# PCB_Project_Wavelength.net
KiCad netlist of a schematic drawn in Altium Designer
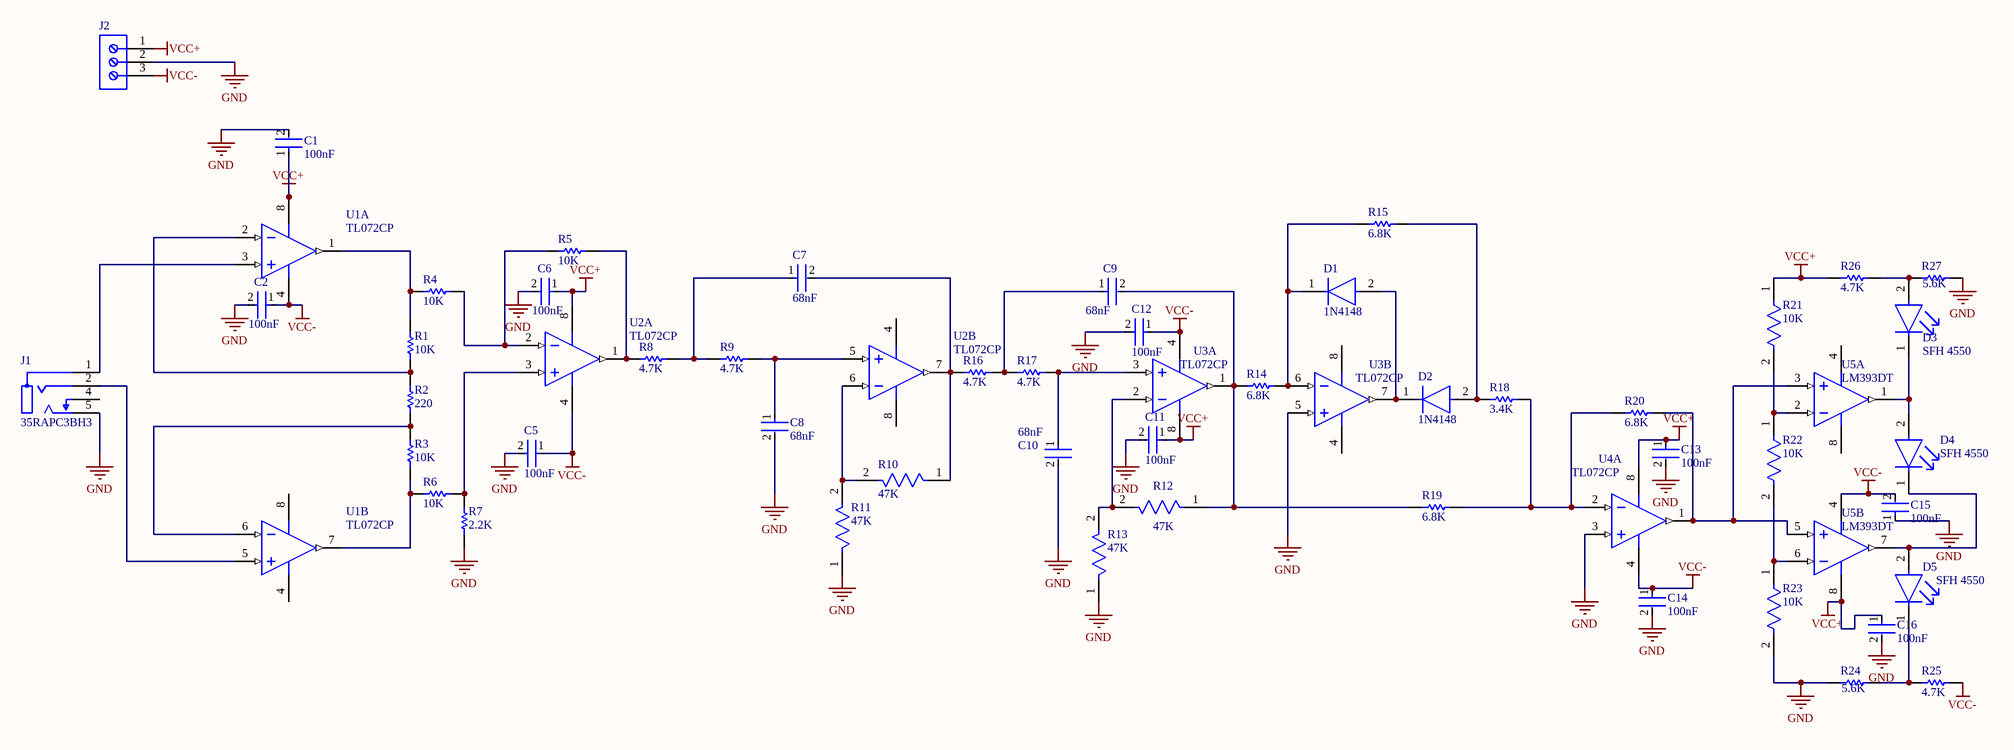
[diagram p0: PCB_Project_Wavelength.SchDoc]

(export (version "E")
  (design (tool "Eeschema 10.0.6"))
  (components
    (comp (ref "C1")
      (value "100nF")
      (footprint "FP-CGA3E-0_3-0_1-IPC_A")
      (description "Cap Ceramic 100nF 50V X7R 10% Pad SMD 0603 +125°C Automotive T/R")
      (fields (field (name "TOLERANCE") "10%") (field (name "VOLTAGE") "50V"))
      (libsource (lib "Altium Content Vault") (part "b4654b650e69147ec39a6b967a45e02"))
    )
    (comp (ref "C2")
      (value "100nF")
      (footprint "FP-CGA3E-0_3-0_1-IPC_A")
      (description "Cap Ceramic 100nF 50V X7R 10% Pad SMD 0603 +125°C Automotive T/R")
      (fields (field (name "TOLERANCE") "10%") (field (name "VOLTAGE") "50V"))
      (libsource (lib "Altium Content Vault") (part "b4654b650e69147ec39a6b967a45e02"))
    )
    (comp (ref "C5")
      (value "100nF")
      (footprint "FP-CGA3E-0_3-0_1-IPC_A")
      (description "Cap Ceramic 100nF 50V X7R 10% Pad SMD 0603 +125°C Automotive T/R")
      (fields (field (name "TOLERANCE") "10%") (field (name "VOLTAGE") "50V"))
      (libsource (lib "Altium Content Vault") (part "b4654b650e69147ec39a6b967a45e02"))
    )
    (comp (ref "C6")
      (value "100nF")
      (footprint "FP-CGA3E-0_3-0_1-IPC_A")
      (description "Cap Ceramic 100nF 50V X7R 10% Pad SMD 0603 +125°C Automotive T/R")
      (fields (field (name "TOLERANCE") "10%") (field (name "VOLTAGE") "50V"))
      (libsource (lib "Altium Content Vault") (part "b4654b650e69147ec39a6b967a45e02"))
    )
    (comp (ref "C7")
      (value "68nF")
      (footprint "FP-1206-L_3_2_0_2-W_1_6_0-IPC_A")
      (description "General Purpose Ceramic Capacitor, 1206, 68nF, 10%, X7R, 15%, 100V")
      (fields (field (name "VOLTAGE") "100V") (field (name "TOLERANCE") "10%"))
      (libsource (lib "Altium Content Vault") (part "02cd4be3c70576c341d710602a673aa"))
    )
    (comp (ref "C8")
      (value "68nF")
      (footprint "FP-1206-L_3_2_0_2-W_1_6_0-IPC_A")
      (description "General Purpose Ceramic Capacitor, 1206, 68nF, 10%, X7R, 15%, 100V")
      (fields (field (name "VOLTAGE") "100V") (field (name "TOLERANCE") "10%"))
      (libsource (lib "Altium Content Vault") (part "02cd4be3c70576c341d710602a673aa"))
    )
    (comp (ref "C9")
      (value "68nF")
      (footprint "FP-1206-L_3_2_0_2-W_1_6_0-IPC_A")
      (description "General Purpose Ceramic Capacitor, 1206, 68nF, 10%, X7R, 15%, 100V")
      (fields (field (name "VOLTAGE") "100V") (field (name "TOLERANCE") "10%"))
      (libsource (lib "Altium Content Vault") (part "02cd4be3c70576c341d710602a673aa"))
    )
    (comp (ref "C10")
      (value "68nF")
      (footprint "FP-1206-L_3_2_0_2-W_1_6_0-IPC_A")
      (description "General Purpose Ceramic Capacitor, 1206, 68nF, 10%, X7R, 15%, 100V")
      (fields (field (name "VOLTAGE") "100V") (field (name "TOLERANCE") "10%"))
      (libsource (lib "Altium Content Vault") (part "02cd4be3c70576c341d710602a673aa"))
    )
    (comp (ref "C11")
      (value "100nF")
      (footprint "FP-CGA3E-0_3-0_1-IPC_A")
      (description "Cap Ceramic 100nF 50V X7R 10% Pad SMD 0603 +125°C Automotive T/R")
      (fields (field (name "TOLERANCE") "10%") (field (name "VOLTAGE") "50V"))
      (libsource (lib "Altium Content Vault") (part "b4654b650e69147ec39a6b967a45e02"))
    )
    (comp (ref "C12")
      (value "100nF")
      (footprint "FP-CGA3E-0_3-0_1-IPC_A")
      (description "Cap Ceramic 100nF 50V X7R 10% Pad SMD 0603 +125°C Automotive T/R")
      (fields (field (name "TOLERANCE") "10%") (field (name "VOLTAGE") "50V"))
      (libsource (lib "Altium Content Vault") (part "b4654b650e69147ec39a6b967a45e02"))
    )
    (comp (ref "C13")
      (value "100nF")
      (footprint "FP-CGA3E-0_3-0_1-IPC_A")
      (description "Cap Ceramic 100nF 50V X7R 10% Pad SMD 0603 +125°C Automotive T/R")
      (fields (field (name "TOLERANCE") "10%") (field (name "VOLTAGE") "50V"))
      (libsource (lib "Altium Content Vault") (part "b4654b650e69147ec39a6b967a45e02"))
    )
    (comp (ref "C14")
      (value "100nF")
      (footprint "FP-CGA3E-0_3-0_1-IPC_A")
      (description "Cap Ceramic 100nF 50V X7R 10% Pad SMD 0603 +125°C Automotive T/R")
      (fields (field (name "TOLERANCE") "10%") (field (name "VOLTAGE") "50V"))
      (libsource (lib "Altium Content Vault") (part "b4654b650e69147ec39a6b967a45e02"))
    )
    (comp (ref "C15")
      (value "100nF")
      (footprint "FP-CGA3E-0_3-0_1-IPC_A")
      (description "Cap Ceramic 100nF 50V X7R 10% Pad SMD 0603 +125°C Automotive T/R")
      (fields (field (name "TOLERANCE") "10%") (field (name "VOLTAGE") "50V"))
      (libsource (lib "Altium Content Vault") (part "b4654b650e69147ec39a6b967a45e02"))
    )
    (comp (ref "C16")
      (value "100nF")
      (footprint "FP-CGA3E-0_3-0_1-IPC_A")
      (description "Cap Ceramic 100nF 50V X7R 10% Pad SMD 0603 +125°C Automotive T/R")
      (fields (field (name "TOLERANCE") "10%") (field (name "VOLTAGE") "50V"))
      (libsource (lib "Altium Content Vault") (part "b4654b650e69147ec39a6b967a45e02"))
    )
    (comp (ref "D1")
      (value "1N4148")
      (footprint "FP-017AG-MFG")
      (description "DIODE GEN PURP 100V 200MA DO35")
      (fields (field (name "VOLTAGE") "100V"))
      (libsource (lib "Altium Content Vault") (part "d7152d700b627762746794eb795d46e"))
    )
    (comp (ref "D2")
      (value "1N4148")
      (footprint "FP-017AG-MFG")
      (description "DIODE GEN PURP 100V 200MA DO35")
      (fields (field (name "VOLTAGE") "100V"))
      (libsource (lib "Altium Content Vault") (part "d7152d700b627762746794eb795d46e"))
    )
    (comp (ref "D3")
      (value "SFH 4550")
      (footprint "FP-SFH_4550-MFG")
      (description "EMITTER IR 860NM 100MA RADIAL")
      (fields
        (field (name "OCTOPART") "https://octopart.com/sfh+4550-osram+opto-55410894")
        (field (name "MANUFACTURER") "Osram Opto")
      )
      (libsource (lib "Altium Content Vault") (part "75a0115997dd6a71327e26aab64f6f8"))
    )
    (comp (ref "D4")
      (value "SFH 4550")
      (footprint "FP-SFH_4550-MFG")
      (description "EMITTER IR 860NM 100MA RADIAL")
      (fields
        (field (name "OCTOPART") "https://octopart.com/sfh+4550-osram+opto-55410894")
        (field (name "MANUFACTURER") "Osram Opto")
      )
      (libsource (lib "Altium Content Vault") (part "75a0115997dd6a71327e26aab64f6f8"))
    )
    (comp (ref "D5")
      (value "SFH 4550")
      (footprint "FP-SFH_4550-MFG")
      (description "EMITTER IR 860NM 100MA RADIAL")
      (fields
        (field (name "OCTOPART") "https://octopart.com/sfh+4550-osram+opto-55410894")
        (field (name "MANUFACTURER") "Osram Opto")
      )
      (libsource (lib "Altium Content Vault") (part "75a0115997dd6a71327e26aab64f6f8"))
    )
    (comp (ref "J1")
      (value "35RAPC3BH3")
      (footprint "FP-35RAPC3BH3-MFG")
      (description "CONN JACK STEREO 3.5MM R/A")
      (libsource (lib "Altium Content Vault") (part "6593a1246df2d7246a2ad7da18ee256"))
    )
    (comp (ref "J2")
      (value "691709710303")
      (footprint "691709710303")
      (description "Battery connector")
      (fields (field (name "VOLTAGE") "300V"))
      (libsource (lib "Altium Content Vault") (part "TBL - 1R - 03P - Screw"))
    )
    (comp (ref "R1")
      (value "10K")
      (footprint "RESC1609X50X30NL8T20")
      (description "Chip Resistor, 10 KOhm, +/- 1%, 100 mW, -55 to 155 degC, 0603 (1608 Metric), RoHS, Tape and Reel")
      (fields (field (name "MANUFACTURER") "Vishay Semiconductor"))
      (libsource (lib "Altium Content Vault") (part "RES-2"))
    )
    (comp (ref "R2")
      (value "220")
      (footprint "RESC2013X70X40NL20T20")
      (fields (field (name "PART NUMBER") "ERJ6ENF2200V") (field (name "MANUFACTURER") "Panasonic"))
      (libsource (lib "Altium Content Vault") (part "RES"))
    )
    (comp (ref "R3")
      (value "10K")
      (footprint "RESC1609X50X30NL8T20")
      (description "Chip Resistor, 10 KOhm, +/- 1%, 100 mW, -55 to 155 degC, 0603 (1608 Metric), RoHS, Tape and Reel")
      (fields (field (name "MANUFACTURER") "Vishay Semiconductor"))
      (libsource (lib "Altium Content Vault") (part "RES-2"))
    )
    (comp (ref "R4")
      (value "10K")
      (footprint "RESC1609X50X30NL8T20")
      (description "Chip Resistor, 10 KOhm, +/- 1%, 100 mW, -55 to 155 degC, 0603 (1608 Metric), RoHS, Tape and Reel")
      (fields (field (name "MANUFACTURER") "Vishay Semiconductor"))
      (libsource (lib "Altium Content Vault") (part "RES-2"))
    )
    (comp (ref "R5")
      (value "10K")
      (footprint "RESC1609X50X30NL8T20")
      (description "Chip Resistor, 10 KOhm, +/- 1%, 100 mW, -55 to 155 degC, 0603 (1608 Metric), RoHS, Tape and Reel")
      (fields (field (name "MANUFACTURER") "Vishay Semiconductor"))
      (libsource (lib "Altium Content Vault") (part "RES-2"))
    )
    (comp (ref "R6")
      (value "10K")
      (footprint "RESC1609X50X30NL8T20")
      (description "Chip Resistor, 10 KOhm, +/- 1%, 100 mW, -55 to 155 degC, 0603 (1608 Metric), RoHS, Tape and Reel")
      (fields (field (name "MANUFACTURER") "Vishay Semiconductor"))
      (libsource (lib "Altium Content Vault") (part "RES-2"))
    )
    (comp (ref "R7")
      (value "2.2K")
      (footprint "RESC1608X55X25LL10T15")
      (fields (field (name "TOLERANCE") "1%") (field (name "MANUFACTURER") "Yageo"))
      (libsource (lib "Altium Content Vault") (part "RES-2"))
    )
    (comp (ref "R8")
      (value "4.7K")
      (footprint "RESC1005X40X25LL05T05")
      (description "Chip Resistor, 4.7 KOhm, +/- 1%, 0.1 W, -55 to 155 degC, 0402 (1005 Metric), RoHS, Tape and Reel")
      (fields (field (name "TOLERANCE") "1%") (field (name "PARTNUMBER") "ERJ-2RKF4701X"))
      (libsource (lib "Altium Content Vault") (part "RES-2"))
    )
    (comp (ref "R9")
      (value "4.7K")
      (footprint "RESC1005X40X25LL05T05")
      (description "Chip Resistor, 4.7 KOhm, +/- 1%, 0.1 W, -55 to 155 degC, 0402 (1005 Metric), RoHS, Tape and Reel")
      (fields (field (name "TOLERANCE") "1%") (field (name "PARTNUMBER") "ERJ-2RKF4701X"))
      (libsource (lib "Altium Content Vault") (part "RES-2"))
    )
    (comp (ref "R10")
      (value "47K")
      (footprint "FP-CRCW0603-e3-IPC_B")
      (description "RES SMD 47K OHM 1% 1/10W 0603")
      (fields (field (name "TOLERANCE") "1%"))
      (libsource (lib "Altium Content Vault") (part "1029c3af85768c4190bb7ad29bc67b5"))
    )
    (comp (ref "R11")
      (value "47K")
      (footprint "FP-CRCW0603-e3-IPC_B")
      (description "RES SMD 47K OHM 1% 1/10W 0603")
      (fields (field (name "TOLERANCE") "1%"))
      (libsource (lib "Altium Content Vault") (part "1029c3af85768c4190bb7ad29bc67b5"))
    )
    (comp (ref "R12")
      (value "47K")
      (footprint "FP-CRCW0603-e3-IPC_B")
      (description "RES SMD 47K OHM 1% 1/10W 0603")
      (fields (field (name "TOLERANCE") "1%"))
      (libsource (lib "Altium Content Vault") (part "1029c3af85768c4190bb7ad29bc67b5"))
    )
    (comp (ref "R13")
      (value "47K")
      (footprint "FP-CRCW0603-e3-IPC_B")
      (description "RES SMD 47K OHM 1% 1/10W 0603")
      (fields (field (name "TOLERANCE") "1%"))
      (libsource (lib "Altium Content Vault") (part "1029c3af85768c4190bb7ad29bc67b5"))
    )
    (comp (ref "R14")
      (value "6.8K")
      (footprint "RESC1609X50X30LL10T20")
      (fields (field (name "PART NUMBER") "CRCW06036K80FKEA") (field (name "MANUFACTURER") "Vishay Dale"))
      (libsource (lib "Altium Content Vault") (part "RES"))
    )
    (comp (ref "R15")
      (value "6.8K")
      (footprint "RESC1609X50X30LL10T20")
      (fields (field (name "PART NUMBER") "CRCW06036K80FKEA") (field (name "MANUFACTURER") "Vishay Dale"))
      (libsource (lib "Altium Content Vault") (part "RES"))
    )
    (comp (ref "R16")
      (value "4.7K")
      (footprint "RESC1005X40X25LL05T05")
      (description "Chip Resistor, 4.7 KOhm, +/- 1%, 0.1 W, -55 to 155 degC, 0402 (1005 Metric), RoHS, Tape and Reel")
      (fields (field (name "TOLERANCE") "1%") (field (name "PARTNUMBER") "ERJ-2RKF4701X"))
      (libsource (lib "Altium Content Vault") (part "RES-2"))
    )
    (comp (ref "R17")
      (value "4.7K")
      (footprint "RESC1005X40X25LL05T05")
      (description "Chip Resistor, 4.7 KOhm, +/- 1%, 0.1 W, -55 to 155 degC, 0402 (1005 Metric), RoHS, Tape and Reel")
      (fields (field (name "TOLERANCE") "1%") (field (name "PARTNUMBER") "ERJ-2RKF4701X"))
      (libsource (lib "Altium Content Vault") (part "RES-2"))
    )
    (comp (ref "R18")
      (value "3.4K")
      (footprint "RESC1609X50X30LL10T20")
      (fields (field (name "MANUFACTURER") "Vishay Dale") (field (name "PART NUMBER") "CRCW06033K40FKEA"))
      (libsource (lib "Altium Content Vault") (part "RES"))
    )
    (comp (ref "R19")
      (value "6.8K")
      (footprint "RESC1609X50X30LL10T20")
      (fields (field (name "PART NUMBER") "CRCW06036K80FKEA") (field (name "MANUFACTURER") "Vishay Dale"))
      (libsource (lib "Altium Content Vault") (part "RES"))
    )
    (comp (ref "R20")
      (value "6.8K")
      (footprint "RESC1609X50X30LL10T20")
      (fields (field (name "PART NUMBER") "CRCW06036K80FKEA") (field (name "MANUFACTURER") "Vishay Dale"))
      (libsource (lib "Altium Content Vault") (part "RES"))
    )
    (comp (ref "R21")
      (value "10K")
      (footprint "FP-MCT0603-IPC_C")
      (description "RES SMD 100 OHM 1% 1/8W 0603")
      (fields (field (name "TOLERANCE") "1%"))
      (libsource (lib "Altium Content Vault") (part "1029c3af85768c4190bb7ad29bc67b5"))
    )
    (comp (ref "R22")
      (value "10K")
      (footprint "FP-MCT0603-IPC_C")
      (description "RES SMD 100 OHM 1% 1/8W 0603")
      (fields (field (name "TOLERANCE") "1%"))
      (libsource (lib "Altium Content Vault") (part "1029c3af85768c4190bb7ad29bc67b5"))
    )
    (comp (ref "R23")
      (value "10K")
      (footprint "FP-MCT0603-IPC_C")
      (description "RES SMD 100 OHM 1% 1/8W 0603")
      (fields (field (name "TOLERANCE") "1%"))
      (libsource (lib "Altium Content Vault") (part "1029c3af85768c4190bb7ad29bc67b5"))
    )
    (comp (ref "R24")
      (value "5.6K")
      (footprint "RESC1005X40X25LL05T05")
      (fields (field (name "MANUFACTURER") "Vishay Dale") (field (name "PART NUMBER") "CRCW04025K60FKED"))
      (libsource (lib "Altium Content Vault") (part "RES"))
    )
    (comp (ref "R25")
      (value "4.7K")
      (footprint "RESC2013X70X40NL20T20")
      (description "Chip Resistor, 4.7 KOhm, +/- 1%, 0.125 W, -55 to 155 degC, 0805 (2012 Metric), RoHS, Tape and Reel")
      (fields (field (name "MANUFACTURER") "Panasonic"))
      (libsource (lib "Altium Content Vault") (part "RES-2"))
    )
    (comp (ref "R26")
      (value "4.7K")
      (footprint "RESC2013X70X40NL20T20")
      (description "Chip Resistor, 4.7 KOhm, +/- 1%, 0.125 W, -55 to 155 degC, 0805 (2012 Metric), RoHS, Tape and Reel")
      (fields (field (name "MANUFACTURER") "Panasonic"))
      (libsource (lib "Altium Content Vault") (part "RES-2"))
    )
    (comp (ref "R27")
      (value "5.6K")
      (footprint "RESC1005X40X25LL05T05")
      (fields (field (name "MANUFACTURER") "Vishay Dale") (field (name "PART NUMBER") "CRCW04025K60FKED"))
      (libsource (lib "Altium Content Vault") (part "RES"))
    )
    (comp (ref "U1")
      (value "TL072CP")
      (footprint "P0008A")
      (fields (field (name "MANUFACTURER") "Texas Instruments"))
      (libsource (lib "Altium Content Vault") (part "TI-AMP-D6-2-8_D"))
    )
    (comp (ref "U2")
      (value "TL072CP")
      (footprint "P0008A")
      (fields (field (name "MANUFACTURER") "Texas Instruments"))
      (libsource (lib "Altium Content Vault") (part "TI-AMP-D6-2-8_D"))
    )
    (comp (ref "U3")
      (value "TL072CP")
      (footprint "P0008A")
      (fields (field (name "MANUFACTURER") "Texas Instruments"))
      (libsource (lib "Altium Content Vault") (part "TI-AMP-D6-2-8_D"))
    )
    (comp (ref "U4")
      (value "TL072CP")
      (footprint "P0008A")
      (fields (field (name "MANUFACTURER") "Texas Instruments"))
      (libsource (lib "Altium Content Vault") (part "TI-AMP-D6-2-8_D"))
    )
    (comp (ref "U5")
      (value "LM393DT")
      (footprint "STM-SO-8_D_L")
      (description "Low-Power, Dual-Voltage Comparator, 2 to 36 V, 0 to 70 degC, 8-Pin SOIC (SO), RoHS, Tape and Reel")
      (fields (field (name "MANUFACTURER") "STMicroelectronics"))
      (libsource (lib "Altium Content Vault") (part "STM-LM393-SO8"))
    )
  )
  (nets
    (net (code "1") (name "GND") (class "Default")
      (node (ref "C1") (pin "2") (pinfunction "2_2") (pintype "passive"))
      (node (ref "C10") (pin "2") (pinfunction "2_2") (pintype "passive"))
      (node (ref "C11") (pin "2") (pinfunction "2_2") (pintype "passive"))
      (node (ref "C12") (pin "2") (pinfunction "2_2") (pintype "passive"))
      (node (ref "C13") (pin "2") (pinfunction "2_2") (pintype "passive"))
      (node (ref "C14") (pin "2") (pinfunction "2_2") (pintype "passive"))
      (node (ref "C15") (pin "1") (pinfunction "1_1") (pintype "passive"))
      (node (ref "C16") (pin "2") (pinfunction "2_2") (pintype "passive"))
      (node (ref "C2") (pin "2") (pinfunction "2_2") (pintype "passive"))
      (node (ref "C5") (pin "2") (pinfunction "2_2") (pintype "passive"))
      (node (ref "C6") (pin "2") (pinfunction "2_2") (pintype "passive"))
      (node (ref "C8") (pin "2") (pinfunction "2_2") (pintype "passive"))
      (node (ref "J1") (pin "5") (pinfunction "5_5") (pintype "passive"))
      (node (ref "J2") (pin "2") (pinfunction "2_2") (pintype "passive"))
      (node (ref "R11") (pin "1") (pinfunction "1_1") (pintype "passive"))
      (node (ref "R13") (pin "1") (pinfunction "1_1") (pintype "passive"))
      (node (ref "R23") (pin "2") (pinfunction "2_2") (pintype "passive"))
      (node (ref "R24") (pin "1") (pinfunction "1_1") (pintype "passive"))
      (node (ref "R27") (pin "2") (pinfunction "2_2") (pintype "passive"))
      (node (ref "R7") (pin "1") (pinfunction "1_1") (pintype "passive"))
      (node (ref "U3") (pin "5") (pinfunction "IN2+_5") (pintype "input"))
      (node (ref "U4") (pin "3") (pinfunction "IN1+_3") (pintype "input"))
    )
    (net (code "2") (name "Net-(C7-Pad1)") (class "Default")
      (node (ref "C7") (pin "1") (pinfunction "1_1") (pintype "passive"))
      (node (ref "R8") (pin "2") (pinfunction "2_2") (pintype "passive"))
      (node (ref "R9") (pin "1") (pinfunction "1_1") (pintype "passive"))
    )
    (net (code "3") (name "Net-(C9-Pad1)") (class "Default")
      (node (ref "C9") (pin "1") (pinfunction "1_1") (pintype "passive"))
      (node (ref "R16") (pin "2") (pinfunction "2_2") (pintype "passive"))
      (node (ref "R17") (pin "1") (pinfunction "1_1") (pintype "passive"))
    )
    (net (code "4") (name "Net-(D1-A)") (class "Default")
      (node (ref "D1") (pin "2") (pinfunction "A_2") (pintype "passive"))
      (node (ref "D2") (pin "1") (pinfunction "C_1") (pintype "passive"))
      (node (ref "U3") (pin "7") (pinfunction "OUT2_7") (pintype "output"))
    )
    (net (code "5") (name "Net-(D1-C)") (class "Default")
      (node (ref "D1") (pin "1") (pinfunction "C_1") (pintype "passive"))
      (node (ref "R14") (pin "2") (pinfunction "2_2") (pintype "passive"))
      (node (ref "R15") (pin "1") (pinfunction "1_1") (pintype "passive"))
      (node (ref "U3") (pin "6") (pinfunction "IN2-_6") (pintype "input"))
    )
    (net (code "6") (name "Net-(D2-A)") (class "Default")
      (node (ref "D2") (pin "2") (pinfunction "A_2") (pintype "passive"))
      (node (ref "R15") (pin "2") (pinfunction "2_2") (pintype "passive"))
      (node (ref "R18") (pin "1") (pinfunction "1_1") (pintype "passive"))
    )
    (net (code "7") (name "Net-(D3-A)") (class "Default")
      (node (ref "D3") (pin "2") (pinfunction "A_2") (pintype "passive"))
      (node (ref "R26") (pin "2") (pinfunction "2_2") (pintype "passive"))
      (node (ref "R27") (pin "1") (pinfunction "1_1") (pintype "passive"))
    )
    (net (code "8") (name "Net-(D3-C)") (class "Default")
      (node (ref "D3") (pin "1") (pinfunction "C_1") (pintype "passive"))
      (node (ref "D4") (pin "2") (pinfunction "A_2") (pintype "passive"))
      (node (ref "U5") (pin "1") (pinfunction "OUT1_1") (pintype "output"))
    )
    (net (code "9") (name "Net-(D4-C)") (class "Default")
      (node (ref "D4") (pin "1") (pinfunction "C_1") (pintype "passive"))
      (node (ref "D5") (pin "2") (pinfunction "A_2") (pintype "passive"))
      (node (ref "U5") (pin "7") (pinfunction "OUT2_7") (pintype "output"))
    )
    (net (code "10") (name "Net-(D5-C)") (class "Default")
      (node (ref "D5") (pin "1") (pinfunction "C_1") (pintype "passive"))
      (node (ref "R24") (pin "2") (pinfunction "2_2") (pintype "passive"))
      (node (ref "R25") (pin "1") (pinfunction "1_1") (pintype "passive"))
    )
    (net (code "11") (name "Net-(U1A-IN1+)") (class "Default")
      (node (ref "J1") (pin "1") (pinfunction "1_1") (pintype "passive"))
      (node (ref "U1") (pin "3") (pinfunction "IN1+_3") (pintype "input"))
    )
    (net (code "12") (name "Net-(U1A-IN1-)") (class "Default")
      (node (ref "R1") (pin "1") (pinfunction "1_1") (pintype "passive"))
      (node (ref "R2") (pin "2") (pinfunction "2_2") (pintype "passive"))
      (node (ref "U1") (pin "2") (pinfunction "IN1-_2") (pintype "input"))
    )
    (net (code "13") (name "Net-(U1A-OUT1)") (class "Default")
      (node (ref "R1") (pin "2") (pinfunction "2_2") (pintype "passive"))
      (node (ref "R4") (pin "2") (pinfunction "2_2") (pintype "passive"))
      (node (ref "U1") (pin "1") (pinfunction "OUT1_1") (pintype "output"))
    )
    (net (code "14") (name "Net-(U1B-IN2+)") (class "Default")
      (node (ref "J1") (pin "2") (pinfunction "2_2") (pintype "passive"))
      (node (ref "U1") (pin "5") (pinfunction "IN2+_5") (pintype "input"))
    )
    (net (code "15") (name "Net-(U1B-IN2-)") (class "Default")
      (node (ref "R2") (pin "1") (pinfunction "1_1") (pintype "passive"))
      (node (ref "R3") (pin "2") (pinfunction "2_2") (pintype "passive"))
      (node (ref "U1") (pin "6") (pinfunction "IN2-_6") (pintype "input"))
    )
    (net (code "16") (name "Net-(U1B-OUT2)") (class "Default")
      (node (ref "R3") (pin "1") (pinfunction "1_1") (pintype "passive"))
      (node (ref "R6") (pin "2") (pinfunction "2_2") (pintype "passive"))
      (node (ref "U1") (pin "7") (pinfunction "OUT2_7") (pintype "output"))
    )
    (net (code "17") (name "Net-(U2A-IN1+)") (class "Default")
      (node (ref "R6") (pin "1") (pinfunction "1_1") (pintype "passive"))
      (node (ref "R7") (pin "2") (pinfunction "2_2") (pintype "passive"))
      (node (ref "U2") (pin "3") (pinfunction "IN1+_3") (pintype "input"))
    )
    (net (code "18") (name "Net-(U2A-IN1-)") (class "Default")
      (node (ref "R4") (pin "1") (pinfunction "1_1") (pintype "passive"))
      (node (ref "R5") (pin "2") (pinfunction "2_2") (pintype "passive"))
      (node (ref "U2") (pin "2") (pinfunction "IN1-_2") (pintype "input"))
    )
    (net (code "19") (name "Net-(U2A-OUT1)") (class "Default")
      (node (ref "R5") (pin "1") (pinfunction "1_1") (pintype "passive"))
      (node (ref "R8") (pin "1") (pinfunction "1_1") (pintype "passive"))
      (node (ref "U2") (pin "1") (pinfunction "OUT1_1") (pintype "output"))
    )
    (net (code "20") (name "Net-(U2B-IN2+)") (class "Default")
      (node (ref "C8") (pin "1") (pinfunction "1_1") (pintype "passive"))
      (node (ref "R9") (pin "2") (pinfunction "2_2") (pintype "passive"))
      (node (ref "U2") (pin "5") (pinfunction "IN2+_5") (pintype "input"))
    )
    (net (code "21") (name "Net-(U2B-IN2-)") (class "Default")
      (node (ref "R10") (pin "2") (pinfunction "2_2") (pintype "passive"))
      (node (ref "R11") (pin "2") (pinfunction "2_2") (pintype "passive"))
      (node (ref "U2") (pin "6") (pinfunction "IN2-_6") (pintype "input"))
    )
    (net (code "22") (name "Net-(U2B-OUT2)") (class "Default")
      (node (ref "C7") (pin "2") (pinfunction "2_2") (pintype "passive"))
      (node (ref "R10") (pin "1") (pinfunction "1_1") (pintype "passive"))
      (node (ref "R16") (pin "1") (pinfunction "1_1") (pintype "passive"))
      (node (ref "U2") (pin "7") (pinfunction "OUT2_7") (pintype "output"))
    )
    (net (code "23") (name "Net-(U3A-IN1+)") (class "Default")
      (node (ref "C10") (pin "1") (pinfunction "1_1") (pintype "passive"))
      (node (ref "R17") (pin "2") (pinfunction "2_2") (pintype "passive"))
      (node (ref "U3") (pin "3") (pinfunction "IN1+_3") (pintype "input"))
    )
    (net (code "24") (name "Net-(U3A-IN1-)") (class "Default")
      (node (ref "R12") (pin "2") (pinfunction "2_2") (pintype "passive"))
      (node (ref "R13") (pin "2") (pinfunction "2_2") (pintype "passive"))
      (node (ref "U3") (pin "2") (pinfunction "IN1-_2") (pintype "input"))
    )
    (net (code "25") (name "Net-(U3A-OUT1)") (class "Default")
      (node (ref "C9") (pin "2") (pinfunction "2_2") (pintype "passive"))
      (node (ref "R12") (pin "1") (pinfunction "1_1") (pintype "passive"))
      (node (ref "R14") (pin "1") (pinfunction "1_1") (pintype "passive"))
      (node (ref "R19") (pin "1") (pinfunction "1_1") (pintype "passive"))
      (node (ref "U3") (pin "1") (pinfunction "OUT1_1") (pintype "output"))
    )
    (net (code "26") (name "Net-(U4A-IN1-)") (class "Default")
      (node (ref "R18") (pin "2") (pinfunction "2_2") (pintype "passive"))
      (node (ref "R19") (pin "2") (pinfunction "2_2") (pintype "passive"))
      (node (ref "R20") (pin "1") (pinfunction "1_1") (pintype "passive"))
      (node (ref "U4") (pin "2") (pinfunction "IN1-_2") (pintype "input"))
    )
    (net (code "27") (name "Net-(U4A-OUT1)") (class "Default")
      (node (ref "R20") (pin "2") (pinfunction "2_2") (pintype "passive"))
      (node (ref "U4") (pin "1") (pinfunction "OUT1_1") (pintype "output"))
      (node (ref "U5") (pin "3") (pinfunction "IN1+_3") (pintype "input"))
      (node (ref "U5") (pin "5") (pinfunction "IN2+_5") (pintype "input"))
    )
    (net (code "28") (name "Net-(U5A-IN1-)") (class "Default")
      (node (ref "R21") (pin "2") (pinfunction "2_2") (pintype "passive"))
      (node (ref "R22") (pin "1") (pinfunction "1_1") (pintype "passive"))
      (node (ref "U5") (pin "2") (pinfunction "IN1-_2") (pintype "input"))
    )
    (net (code "29") (name "Net-(U5B-IN2-)") (class "Default")
      (node (ref "R22") (pin "2") (pinfunction "2_2") (pintype "passive"))
      (node (ref "R23") (pin "1") (pinfunction "1_1") (pintype "passive"))
      (node (ref "U5") (pin "6") (pinfunction "IN2-_6") (pintype "input"))
    )
    (net (code "30") (name "VCC+") (class "Default")
      (node (ref "C1") (pin "1") (pinfunction "1_1") (pintype "passive"))
      (node (ref "C11") (pin "1") (pinfunction "1_1") (pintype "passive"))
      (node (ref "C13") (pin "1") (pinfunction "1_1") (pintype "passive"))
      (node (ref "C16") (pin "1") (pinfunction "1_1") (pintype "passive"))
      (node (ref "C6") (pin "1") (pinfunction "1_1") (pintype "passive"))
      (node (ref "J2") (pin "1") (pinfunction "1_1") (pintype "passive"))
      (node (ref "R21") (pin "1") (pinfunction "1_1") (pintype "passive"))
      (node (ref "R26") (pin "1") (pinfunction "1_1") (pintype "passive"))
      (node (ref "U1") (pin "8") (pinfunction "VCC+_8") (pintype "power_in"))
      (node (ref "U2") (pin "8") (pinfunction "VCC+_8") (pintype "power_in"))
      (node (ref "U3") (pin "8") (pinfunction "VCC+_8") (pintype "power_in"))
      (node (ref "U4") (pin "8") (pinfunction "VCC+_8") (pintype "power_in"))
      (node (ref "U5") (pin "8") (pinfunction "VCC+_8") (pintype "power_in"))
    )
    (net (code "31") (name "VCC-") (class "Default")
      (node (ref "C12") (pin "1") (pinfunction "1_1") (pintype "passive"))
      (node (ref "C14") (pin "1") (pinfunction "1_1") (pintype "passive"))
      (node (ref "C15") (pin "2") (pinfunction "2_2") (pintype "passive"))
      (node (ref "C2") (pin "1") (pinfunction "1_1") (pintype "passive"))
      (node (ref "C5") (pin "1") (pinfunction "1_1") (pintype "passive"))
      (node (ref "J2") (pin "3") (pinfunction "3_3") (pintype "passive"))
      (node (ref "R25") (pin "2") (pinfunction "2_2") (pintype "passive"))
      (node (ref "U1") (pin "4") (pinfunction "VCC-_4") (pintype "power_in"))
      (node (ref "U2") (pin "4") (pinfunction "VCC-_4") (pintype "power_in"))
      (node (ref "U3") (pin "4") (pinfunction "VCC-_4") (pintype "power_in"))
      (node (ref "U4") (pin "4") (pinfunction "VCC-_4") (pintype "power_in"))
      (node (ref "U5") (pin "4") (pinfunction "VCC-_4") (pintype "power_in"))
    )
    (net (code "32") (name "unconnected-(J1-Pad4)") (class "Default")
      (node (ref "J1") (pin "4") (pinfunction "4_4") (pintype "passive"))
    )
    (net (code "33") (name "unconnected-(U1B-VCC+-Pad8)") (class "Default")
      (node (ref "U1") (pin "8") (pinfunction "VCC+_8") (pintype "power_in"))
    )
    (net (code "34") (name "unconnected-(U1B-VCC--Pad4)") (class "Default")
      (node (ref "U1") (pin "4") (pinfunction "VCC-_4") (pintype "power_in"))
    )
    (net (code "35") (name "unconnected-(U2B-VCC+-Pad8)") (class "Default")
      (node (ref "U2") (pin "8") (pinfunction "VCC+_8") (pintype "power_in"))
    )
    (net (code "36") (name "unconnected-(U2B-VCC--Pad4)") (class "Default")
      (node (ref "U2") (pin "4") (pinfunction "VCC-_4") (pintype "power_in"))
    )
    (net (code "37") (name "unconnected-(U3B-VCC+-Pad8)") (class "Default")
      (node (ref "U3") (pin "8") (pinfunction "VCC+_8") (pintype "power_in"))
    )
    (net (code "38") (name "unconnected-(U3B-VCC--Pad4)") (class "Default")
      (node (ref "U3") (pin "4") (pinfunction "VCC-_4") (pintype "power_in"))
    )
    (net (code "39") (name "unconnected-(U5A-VCC+-Pad8)") (class "Default")
      (node (ref "U5") (pin "8") (pinfunction "VCC+_8") (pintype "power_in"))
    )
    (net (code "40") (name "unconnected-(U5A-VCC--Pad4)") (class "Default")
      (node (ref "U5") (pin "4") (pinfunction "VCC-_4") (pintype "power_in"))
    )
  )
)
